# Bypass_FPGA_2V5.net
KiCad netlist of a schematic drawn in Altium Designer
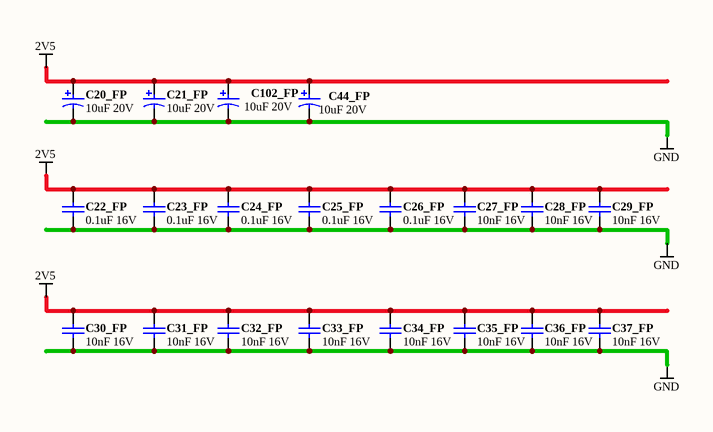
[diagram p0: Bypass_FPGA_2V5.SchDoc]

(export (version "E")
  (design (tool "Eeschema 10.0.6"))
  (components
    (comp (ref "C20_FP")
      (value "10uF 20V")
      (footprint "CAPC3528-STAR")
      (description "Capacitor, Tantalum, 10uF 10% 20V MCCT-B (3528)")
      (fields (field (name "TOLERANCE") "10 %"))
      (libsource (lib "altium-import") (part "root_0_CAP-P_"))
    )
    (comp (ref "C21_FP")
      (value "10uF 20V")
      (footprint "CAPC3528-STAR")
      (description "Capacitor, Tantalum, 10uF 10% 20V MCCT-B (3528)")
      (fields (field (name "TOLERANCE") "10 %"))
      (libsource (lib "altium-import") (part "root_0_CAP-P_"))
    )
    (comp (ref "C22_FP")
      (value "0.1uF 16V")
      (footprint "CAPC1005-STAR")
      (description "Capacitor, Ceramic, 0.1uF 10% 16V 0402 (1005) X7R")
      (fields (field (name "TOLERANCE") "10 %"))
      (libsource (lib "altium-import") (part "root_0_mirrored_CAP-NP_"))
    )
    (comp (ref "C23_FP")
      (value "0.1uF 16V")
      (footprint "CAPC1005-STAR")
      (description "Capacitor, Ceramic, 0.1uF 10% 16V 0402 (1005) X7R")
      (fields (field (name "TOLERANCE") "10 %"))
      (libsource (lib "altium-import") (part "root_0_mirrored_CAP-NP_"))
    )
    (comp (ref "C24_FP")
      (value "0.1uF 16V")
      (footprint "CAPC1005-STAR")
      (description "Capacitor, Ceramic, 0.1uF 10% 16V 0402 (1005) X7R")
      (fields (field (name "TOLERANCE") "10 %"))
      (libsource (lib "altium-import") (part "root_0_mirrored_CAP-NP_"))
    )
    (comp (ref "C25_FP")
      (value "0.1uF 16V")
      (footprint "CAPC1005-STAR")
      (description "Capacitor, Ceramic, 0.1uF 10% 16V 0402 (1005) X7R")
      (fields (field (name "TOLERANCE") "10 %"))
      (libsource (lib "altium-import") (part "root_0_mirrored_CAP-NP_"))
    )
    (comp (ref "C26_FP")
      (value "0.1uF 16V")
      (footprint "CAPC1005-STAR")
      (description "Capacitor, Ceramic, 0.1uF 10% 16V 0402 (1005) X7R")
      (fields (field (name "TOLERANCE") "10 %"))
      (libsource (lib "altium-import") (part "root_0_mirrored_CAP-NP_"))
    )
    (comp (ref "C27_FP")
      (value "10nF 16V")
      (footprint "CAPC1005-STAR")
      (description "Capacitor, Ceramic, 10nF 10% 16V 0402 (1005) X7R")
      (fields (field (name "TOLERANCE") "10 %"))
      (libsource (lib "altium-import") (part "root_0_CAP-NP_"))
    )
    (comp (ref "C28_FP")
      (value "10nF 16V")
      (footprint "CAPC1005-STAR")
      (description "Capacitor, Ceramic, 10nF 10% 16V 0402 (1005) X7R")
      (fields (field (name "TOLERANCE") "10 %"))
      (libsource (lib "altium-import") (part "root_0_CAP-NP_"))
    )
    (comp (ref "C29_FP")
      (value "10nF 16V")
      (footprint "CAPC1005-STAR")
      (description "Capacitor, Ceramic, 10nF 10% 16V 0402 (1005) X7R")
      (fields (field (name "TOLERANCE") "10 %"))
      (libsource (lib "altium-import") (part "root_0_CAP-NP_"))
    )
    (comp (ref "C30_FP")
      (value "10nF 16V")
      (footprint "CAPC1005-STAR")
      (description "Capacitor, Ceramic, 10nF 10% 16V 0402 (1005) X7R")
      (fields (field (name "TOLERANCE") "10 %"))
      (libsource (lib "altium-import") (part "root_0_CAP-NP_"))
    )
    (comp (ref "C31_FP")
      (value "10nF 16V")
      (footprint "CAPC1005-STAR")
      (description "Capacitor, Ceramic, 10nF 10% 16V 0402 (1005) X7R")
      (fields (field (name "TOLERANCE") "10 %"))
      (libsource (lib "altium-import") (part "root_0_CAP-NP_"))
    )
    (comp (ref "C32_FP")
      (value "10nF 16V")
      (footprint "CAPC1005-STAR")
      (description "Capacitor, Ceramic, 10nF 10% 16V 0402 (1005) X7R")
      (fields (field (name "TOLERANCE") "10 %"))
      (libsource (lib "altium-import") (part "root_0_CAP-NP_"))
    )
    (comp (ref "C33_FP")
      (value "10nF 16V")
      (footprint "CAPC1005-STAR")
      (description "Capacitor, Ceramic, 10nF 10% 16V 0402 (1005) X7R")
      (fields (field (name "TOLERANCE") "10 %"))
      (libsource (lib "altium-import") (part "root_0_CAP-NP_"))
    )
    (comp (ref "C34_FP")
      (value "10nF 16V")
      (footprint "CAPC1005-STAR")
      (description "Capacitor, Ceramic, 10nF 10% 16V 0402 (1005) X7R")
      (fields (field (name "TOLERANCE") "10 %"))
      (libsource (lib "altium-import") (part "root_0_CAP-NP_"))
    )
    (comp (ref "C35_FP")
      (value "10nF 16V")
      (footprint "CAPC1005-STAR")
      (description "Capacitor, Ceramic, 10nF 10% 16V 0402 (1005) X7R")
      (fields (field (name "TOLERANCE") "10 %"))
      (libsource (lib "altium-import") (part "root_0_CAP-NP_"))
    )
    (comp (ref "C36_FP")
      (value "10nF 16V")
      (footprint "CAPC1005-STAR")
      (description "Capacitor, Ceramic, 10nF 10% 16V 0402 (1005) X7R")
      (fields (field (name "TOLERANCE") "10 %"))
      (libsource (lib "altium-import") (part "root_0_CAP-NP_"))
    )
    (comp (ref "C37_FP")
      (value "10nF 16V")
      (footprint "CAPC1005-STAR")
      (description "Capacitor, Ceramic, 10nF 10% 16V 0402 (1005) X7R")
      (fields (field (name "TOLERANCE") "10 %"))
      (libsource (lib "altium-import") (part "root_0_CAP-NP_"))
    )
    (comp (ref "C44_FP")
      (value "10uF 20V")
      (footprint "CAPC3528-STAR")
      (description "Capacitor, Tantalum, 10uF 10% 20V MCCT-B (3528)")
      (fields (field (name "TOLERANCE") "10 %"))
      (libsource (lib "altium-import") (part "root_0_CAP-P_"))
    )
    (comp (ref "C102_FP")
      (value "10uF 20V")
      (footprint "CAPC3528-STAR")
      (description "Capacitor, Tantalum, 10uF 10% 20V MCCT-B (3528)")
      (fields (field (name "TOLERANCE") "10 %"))
      (libsource (lib "altium-import") (part "root_0_CAP-P_"))
    )
  )
  (nets
    (net (code "1") (name "2V5") (class "Default")
      (node (ref "C102_FP") (pin "1") (pinfunction "1_1") (pintype "passive"))
      (node (ref "C20_FP") (pin "1") (pinfunction "1_1") (pintype "passive"))
      (node (ref "C21_FP") (pin "1") (pinfunction "1_1") (pintype "passive"))
      (node (ref "C22_FP") (pin "1") (pinfunction "1_1") (pintype "passive"))
      (node (ref "C23_FP") (pin "1") (pinfunction "1_1") (pintype "passive"))
      (node (ref "C24_FP") (pin "1") (pinfunction "1_1") (pintype "passive"))
      (node (ref "C25_FP") (pin "1") (pinfunction "1_1") (pintype "passive"))
      (node (ref "C26_FP") (pin "1") (pinfunction "1_1") (pintype "passive"))
      (node (ref "C27_FP") (pin "1") (pinfunction "1_1") (pintype "passive"))
      (node (ref "C28_FP") (pin "1") (pinfunction "1_1") (pintype "passive"))
      (node (ref "C29_FP") (pin "1") (pinfunction "1_1") (pintype "passive"))
      (node (ref "C30_FP") (pin "1") (pinfunction "1_1") (pintype "passive"))
      (node (ref "C31_FP") (pin "1") (pinfunction "1_1") (pintype "passive"))
      (node (ref "C32_FP") (pin "1") (pinfunction "1_1") (pintype "passive"))
      (node (ref "C33_FP") (pin "1") (pinfunction "1_1") (pintype "passive"))
      (node (ref "C34_FP") (pin "1") (pinfunction "1_1") (pintype "passive"))
      (node (ref "C35_FP") (pin "1") (pinfunction "1_1") (pintype "passive"))
      (node (ref "C36_FP") (pin "1") (pinfunction "1_1") (pintype "passive"))
      (node (ref "C37_FP") (pin "1") (pinfunction "1_1") (pintype "passive"))
      (node (ref "C44_FP") (pin "1") (pinfunction "1_1") (pintype "passive"))
    )
    (net (code "2") (name "GND") (class "Default")
      (node (ref "C102_FP") (pin "2") (pinfunction "2_2") (pintype "passive"))
      (node (ref "C20_FP") (pin "2") (pinfunction "2_2") (pintype "passive"))
      (node (ref "C21_FP") (pin "2") (pinfunction "2_2") (pintype "passive"))
      (node (ref "C22_FP") (pin "2") (pinfunction "2_2") (pintype "passive"))
      (node (ref "C23_FP") (pin "2") (pinfunction "2_2") (pintype "passive"))
      (node (ref "C24_FP") (pin "2") (pinfunction "2_2") (pintype "passive"))
      (node (ref "C25_FP") (pin "2") (pinfunction "2_2") (pintype "passive"))
      (node (ref "C26_FP") (pin "2") (pinfunction "2_2") (pintype "passive"))
      (node (ref "C27_FP") (pin "2") (pinfunction "2_2") (pintype "passive"))
      (node (ref "C28_FP") (pin "2") (pinfunction "2_2") (pintype "passive"))
      (node (ref "C29_FP") (pin "2") (pinfunction "2_2") (pintype "passive"))
      (node (ref "C30_FP") (pin "2") (pinfunction "2_2") (pintype "passive"))
      (node (ref "C31_FP") (pin "2") (pinfunction "2_2") (pintype "passive"))
      (node (ref "C32_FP") (pin "2") (pinfunction "2_2") (pintype "passive"))
      (node (ref "C33_FP") (pin "2") (pinfunction "2_2") (pintype "passive"))
      (node (ref "C34_FP") (pin "2") (pinfunction "2_2") (pintype "passive"))
      (node (ref "C35_FP") (pin "2") (pinfunction "2_2") (pintype "passive"))
      (node (ref "C36_FP") (pin "2") (pinfunction "2_2") (pintype "passive"))
      (node (ref "C37_FP") (pin "2") (pinfunction "2_2") (pintype "passive"))
      (node (ref "C44_FP") (pin "2") (pinfunction "2_2") (pintype "passive"))
    )
  )
)
